# jn5168_blk.net
KiCad netlist of a schematic drawn in Altium Designer
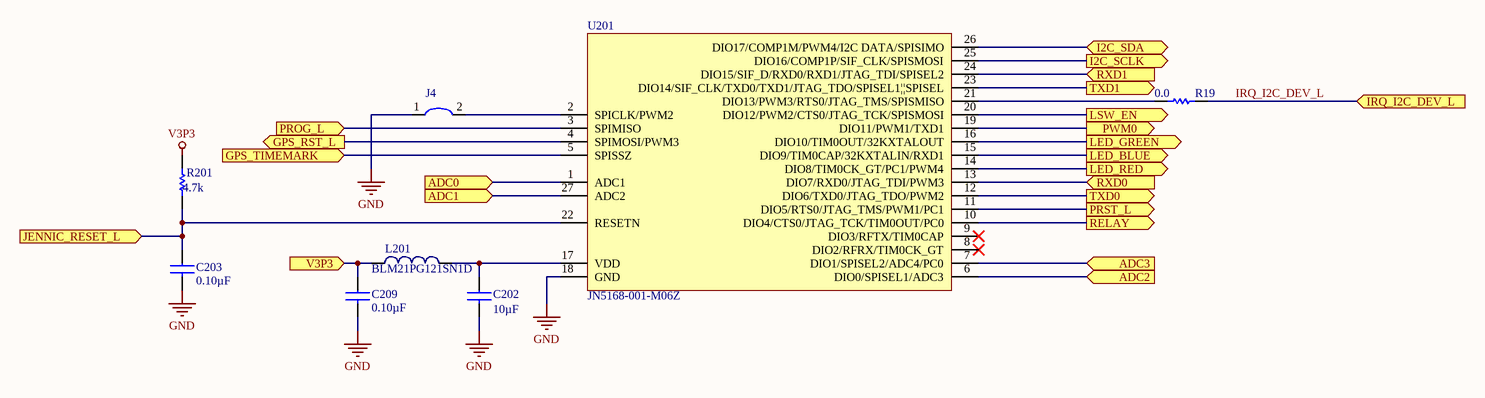
[diagram p0: jn5168_blk.SchDoc]

(export (version "E")
  (design (tool "Eeschema 10.0.6"))
  (components
    (comp (ref "C202")
      (value "10µF")
      (footprint "C1206")
      (description "CAP CER 10UF 16V X7R 1206")
      (fields (field (name "MPN") "GRM31CR71C106KAC7L"))
      (libsource (lib "Capacitor") (part "GRM31CR71C106KAC7L"))
    )
    (comp (ref "C203")
      (value "0.10µF")
      (footprint "C0402")
      (description "CAP CER 0.1UF 50V X7R 0402")
      (fields (field (name "MPN") "GRM155R71H104ME14D"))
      (libsource (lib "Capacitor") (part "GRM155R71H104ME14D"))
    )
    (comp (ref "C209")
      (value "0.10µF")
      (footprint "C0402")
      (description "CAP CER 0.1UF 50V X7R 0402")
      (fields (field (name "MPN") "GRM155R71H104ME14D"))
      (libsource (lib "Capacitor") (part "GRM155R71H104ME14D"))
    )
    (comp (ref "J4")
      (value "0603 Jumper")
      (footprint "0603 Jumper")
      (libsource (lib "Connector") (part "0603 Jumper"))
    )
    (comp (ref "L201")
      (value "BLM21PG121SN1D")
      (footprint "0805 INDUCTOR")
      (description "FERRITE CHIP 120 OHM 0805")
      (fields (field (name "MPN") "BLM21PG121SN1D"))
      (libsource (lib "Inductor") (part "BLM21PG121SN1D"))
    )
    (comp (ref "R19")
      (value "0.0")
      (footprint "R0402")
      (description "RES SMD 0.0OHM JUMPER 1/16W 0402")
      (fields (field (name "MPN") "CRCW04020000Z0ED"))
      (libsource (lib "Res") (part "CRCW04020000Z0ED"))
    )
    (comp (ref "R201")
      (value "4.7k")
      (footprint "R0402")
      (description "RES SMD 4.7K OHM 1% 1/10W 0402")
      (fields (field (name "MPN") "ERJ-2RKF4701X"))
      (libsource (lib "Res") (part "ERJ-2RKF4701X"))
    )
    (comp (ref "U201")
      (value "JN5168-001-M06Z")
      (footprint "JN5168-001-M06Z")
      (description "RF TXRX MODULE 802.15.4 U.FL ANT")
      (fields (field (name "MPN") "JN5168-001-M06Z"))
      (libsource (lib "Module") (part "JN5168-001-M06Z"))
    )
  )
  (nets
    (net (code "1") (name "/ADC0") (class "Default")
      (node (ref "U201") (pin "1") (pinfunction "ADC1_1") (pintype "passive"))
    )
    (net (code "2") (name "/ADC1") (class "Default")
      (node (ref "U201") (pin "27") (pinfunction "ADC2_27") (pintype "passive"))
    )
    (net (code "3") (name "/ADC2") (class "Default")
      (node (ref "U201") (pin "6") (pinfunction "DIO0/SPISEL1/ADC3_6") (pintype "passive"))
    )
    (net (code "4") (name "/ADC3") (class "Default")
      (node (ref "U201") (pin "7") (pinfunction "DIO1/SPISEL2/ADC4/PC0_7") (pintype "passive"))
    )
    (net (code "5") (name "/GPS_RST_L") (class "Default")
      (node (ref "U201") (pin "4") (pinfunction "SPIMOSI/PWM3_4") (pintype "passive"))
    )
    (net (code "6") (name "/GPS_TIMEMARK") (class "Default")
      (node (ref "U201") (pin "5") (pinfunction "SPISSZ_5") (pintype "passive"))
    )
    (net (code "7") (name "/I2C_SCLK") (class "Default")
      (node (ref "U201") (pin "25") (pinfunction "DIO16/COMP1P/SIF_CLK/SPISMOSI_25") (pintype "passive"))
    )
    (net (code "8") (name "/I2C_SDA") (class "Default")
      (node (ref "U201") (pin "26") (pinfunction "DIO17/COMP1M/PWM4/I2C_DATA/SPISIMO_26") (pintype "passive"))
    )
    (net (code "9") (name "/IRQ_I2C_DEV_L") (class "Default")
      (node (ref "R19") (pin "2") (pinfunction "2_2") (pintype "passive"))
    )
    (net (code "10") (name "/JENNIC_RESET_L") (class "Default")
      (node (ref "C203") (pin "1") (pinfunction "1_1") (pintype "passive"))
      (node (ref "R201") (pin "1") (pinfunction "1_1") (pintype "passive"))
      (node (ref "U201") (pin "22") (pinfunction "RESETN_22") (pintype "passive"))
    )
    (net (code "11") (name "/LED_BLUE") (class "Default")
      (node (ref "U201") (pin "15") (pinfunction "DIO9/TIM0CAP/32KXTALIN/RXD1_15") (pintype "passive"))
    )
    (net (code "12") (name "/LED_GREEN") (class "Default")
      (node (ref "U201") (pin "16") (pinfunction "DIO10/TIM0OUT/32KXTALOUT_16") (pintype "passive"))
    )
    (net (code "13") (name "/LED_RED") (class "Default")
      (node (ref "U201") (pin "14") (pinfunction "DIO8/TIM0CK_GT/PC1/PWM4_14") (pintype "passive"))
    )
    (net (code "14") (name "/LSW_EN") (class "Default")
      (node (ref "U201") (pin "20") (pinfunction "DIO12/PWM2/CTS0/JTAG_TCK/SPISMOSI_20") (pintype "passive"))
    )
    (net (code "15") (name "/PROG_L") (class "Default")
      (node (ref "U201") (pin "3") (pinfunction "SPIMISO_3") (pintype "passive"))
    )
    (net (code "16") (name "/PRST_L") (class "Default")
      (node (ref "U201") (pin "11") (pinfunction "DIO5/RTS0/JTAG_TMS/PWM1/PC1_11") (pintype "passive"))
    )
    (net (code "17") (name "/PWM0") (class "Default")
      (node (ref "U201") (pin "19") (pinfunction "DIO11/PWM1/TXD1_19") (pintype "passive"))
    )
    (net (code "18") (name "/RELAY") (class "Default")
      (node (ref "U201") (pin "10") (pinfunction "DIO4/CTS0/JTAG_TCK/TIM0OUT/PC0_10") (pintype "passive"))
    )
    (net (code "19") (name "/RXD0") (class "Default")
      (node (ref "U201") (pin "13") (pinfunction "DIO7/RXD0/JTAG_TDI/PWM3_13") (pintype "passive"))
    )
    (net (code "20") (name "/RXD1") (class "Default")
      (node (ref "U201") (pin "24") (pinfunction "DIO15/SIF_D/RXD0/RXD1/JTAG_TDI/SPISEL2_24") (pintype "passive"))
    )
    (net (code "21") (name "/TXD0") (class "Default")
      (node (ref "U201") (pin "12") (pinfunction "DIO6/TXD0/JTAG_TDO/PWM2_12") (pintype "passive"))
    )
    (net (code "22") (name "/TXD1") (class "Default")
      (node (ref "U201") (pin "23") (pinfunction "DIO14/SIF_CLK/TXD0/TXD1/JTAG_TDO/SPISEL1ΖSPISEL_23") (pintype "passive"))
    )
    (net (code "23") (name "GND") (class "Default")
      (node (ref "C202") (pin "2") (pinfunction "2_2") (pintype "passive"))
      (node (ref "C203") (pin "2") (pinfunction "2_2") (pintype "passive"))
      (node (ref "C209") (pin "2") (pinfunction "2_2") (pintype "passive"))
      (node (ref "J4") (pin "1") (pinfunction "1_1") (pintype "passive"))
      (node (ref "U201") (pin "18") (pinfunction "GND_18") (pintype "passive"))
    )
    (net (code "24") (name "Net-(U201-DIO13{slash}PWM3{slash}RTS0{slash}JTAG_TMS{slash}SPISMISO)") (class "Default")
      (node (ref "R19") (pin "1") (pinfunction "1_1") (pintype "passive"))
      (node (ref "U201") (pin "21") (pinfunction "DIO13/PWM3/RTS0/JTAG_TMS/SPISMISO_21") (pintype "passive"))
    )
    (net (code "25") (name "Net-(U201-SPICLK{slash}PWM2)") (class "Default")
      (node (ref "J4") (pin "2") (pinfunction "2_2") (pintype "passive"))
      (node (ref "U201") (pin "2") (pinfunction "SPICLK/PWM2_2") (pintype "passive"))
    )
    (net (code "26") (name "Net-(U201-VDD)") (class "Default")
      (node (ref "C202") (pin "1") (pinfunction "1_1") (pintype "passive"))
      (node (ref "L201") (pin "1") (pinfunction "1_1") (pintype "passive"))
      (node (ref "U201") (pin "17") (pinfunction "VDD_17") (pintype "passive"))
    )
    (net (code "27") (name "V3P3") (class "Default")
      (node (ref "C209") (pin "1") (pinfunction "1_1") (pintype "passive"))
      (node (ref "L201") (pin "2") (pinfunction "2_2") (pintype "passive"))
      (node (ref "R201") (pin "2") (pinfunction "2_2") (pintype "passive"))
    )
    (net (code "28") (name "unconnected-(U201-DIO2{slash}RFRX{slash}TIM0CK_GT-Pad8)") (class "Default")
      (node (ref "U201") (pin "8") (pinfunction "DIO2/RFRX/TIM0CK_GT_8") (pintype "passive+no_connect"))
    )
    (net (code "29") (name "unconnected-(U201-DIO3{slash}RFTX{slash}TIM0CAP-Pad9)") (class "Default")
      (node (ref "U201") (pin "9") (pinfunction "DIO3/RFTX/TIM0CAP_9") (pintype "passive+no_connect"))
    )
  )
)
